# USB-UART.net
KiCad netlist of a schematic drawn in Altium Designer
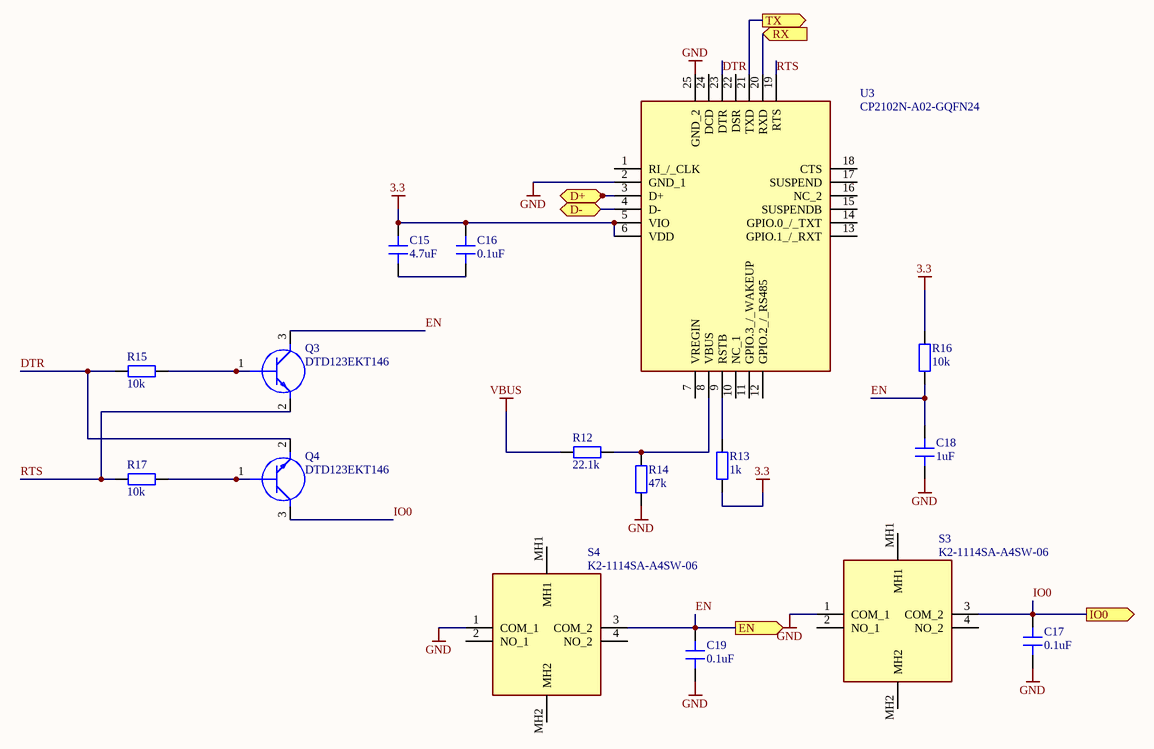
[diagram p0: USB-UART.SchDoc]

(export (version "E")
  (design (tool "Eeschema 10.0.6"))
  (components
    (comp (ref "C15")
      (value "4.7uF")
      (footprint "0603_CAP")
      (libsource (lib "passive_components") (part "C"))
    )
    (comp (ref "C16")
      (value "0.1uF")
      (footprint "0603_CAP")
      (libsource (lib "passive_components") (part "C"))
    )
    (comp (ref "C17")
      (value "0.1uF")
      (footprint "0603_CAP")
      (libsource (lib "passive_components") (part "C"))
    )
    (comp (ref "C18") (value "1uF") (footprint "0603_CAP") (libsource (lib "passive_components") (part "C")))
    (comp (ref "C19")
      (value "0.1uF")
      (footprint "0603_CAP")
      (libsource (lib "passive_components") (part "C"))
    )
    (comp (ref "Q3")
      (value "DTD123EKT146")
      (footprint "FP-SS8050-G-IPC_A")
      (description "Transistor BJT NPN")
      (fields (field (name "MOUSER PART NUMBER") "755-DTD123EKT146"))
      (libsource (lib "test") (part "DTD123EKT146"))
    )
    (comp (ref "Q4")
      (value "DTD123EKT146")
      (footprint "FP-SS8050-G-IPC_A")
      (description "Transistor BJT NPN")
      (fields (field (name "MOUSER PART NUMBER") "755-DTD123EKT146"))
      (libsource (lib "test") (part "DTD123EKT146"))
    )
    (comp (ref "R12")
      (value "22.1k")
      (footprint "0402_RES")
      (libsource (lib "passive_components") (part "R"))
    )
    (comp (ref "R13") (value "1k") (footprint "0402_RES") (libsource (lib "passive_components") (part "R")))
    (comp (ref "R14") (value "47k") (footprint "0402_RES") (libsource (lib "passive_components") (part "R")))
    (comp (ref "R15") (value "10k") (footprint "0402_RES") (libsource (lib "passive_components") (part "R")))
    (comp (ref "R16") (value "10k") (footprint "0402_RES") (libsource (lib "passive_components") (part "R")))
    (comp (ref "R17") (value "10k") (footprint "0402_RES") (libsource (lib "passive_components") (part "R")))
    (comp (ref "S3")
      (value "K2-1114SA-A4SW-06")
      (footprint "K21114SAA4SW06")
      (description "Switch")
      (libsource (lib "PushButton_v01") (part "K2-1114SA-A4SW-06"))
    )
    (comp (ref "S4")
      (value "K2-1114SA-A4SW-06")
      (footprint "K21114SAA4SW06")
      (description "Switch")
      (libsource (lib "PushButton_v01") (part "K2-1114SA-A4SW-06"))
    )
    (comp (ref "U3")
      (value "CP2102N-A02-GQFN24")
      (footprint "FP-CP2102N-A02-GQFN24-MFG")
      (description "Integrated Circuit")
      (fields (field (name "MOUSER PART NUMBER") "634-CP2102NA02GQFN24"))
      (libsource (lib "cp2102n_v01") (part "CP2102N-A02-GQFN24"))
    )
  )
  (nets
    (net (code "1") (name "/D+") (class "Default")
      (node (ref "U3") (pin "3") (pinfunction "D+_3") (pintype "passive"))
    )
    (net (code "2") (name "/D-") (class "Default")
      (node (ref "U3") (pin "4") (pinfunction "D-_4") (pintype "passive"))
    )
    (net (code "3") (name "/DTR") (class "Default")
      (node (ref "Q4") (pin "2") (pinfunction "E_2") (pintype "passive"))
      (node (ref "R15") (pin "1") (pinfunction "25_1") (pintype "passive"))
      (node (ref "U3") (pin "23") (pinfunction "DTR_23") (pintype "passive"))
    )
    (net (code "4") (name "/EN") (class "Default")
      (node (ref "C18") (pin "2") (pinfunction "28_2") (pintype "passive"))
      (node (ref "C19") (pin "1") (pinfunction "1_1") (pintype "passive"))
      (node (ref "Q3") (pin "3") (pinfunction "C_3") (pintype "passive"))
      (node (ref "R16") (pin "2") (pinfunction "26_2") (pintype "passive"))
      (node (ref "S4") (pin "3") (pinfunction "COM_2_3") (pintype "passive"))
    )
    (net (code "5") (name "/IO0") (class "Default")
      (node (ref "C17") (pin "1") (pinfunction "1_1") (pintype "passive"))
      (node (ref "Q4") (pin "3") (pinfunction "C_3") (pintype "passive"))
      (node (ref "S3") (pin "3") (pinfunction "COM_2_3") (pintype "passive"))
    )
    (net (code "6") (name "/RTS") (class "Default")
      (node (ref "Q3") (pin "2") (pinfunction "E_2") (pintype "passive"))
      (node (ref "R17") (pin "1") (pinfunction "25_1") (pintype "passive"))
      (node (ref "U3") (pin "19") (pinfunction "RTS_19") (pintype "passive"))
    )
    (net (code "7") (name "/RX") (class "Default")
      (node (ref "U3") (pin "20") (pinfunction "RXD_20") (pintype "passive"))
    )
    (net (code "8") (name "/TX") (class "Default")
      (node (ref "U3") (pin "21") (pinfunction "TXD_21") (pintype "passive"))
    )
    (net (code "9") (name "3.3") (class "Default")
      (node (ref "C15") (pin "1") (pinfunction "1_1") (pintype "passive"))
      (node (ref "C16") (pin "1") (pinfunction "1_1") (pintype "passive"))
      (node (ref "R13") (pin "2") (pinfunction "26_2") (pintype "passive"))
      (node (ref "R16") (pin "1") (pinfunction "25_1") (pintype "passive"))
      (node (ref "U3") (pin "5") (pinfunction "VIO_5") (pintype "passive"))
      (node (ref "U3") (pin "6") (pinfunction "VDD_6") (pintype "passive"))
    )
    (net (code "10") (name "GND") (class "Default")
      (node (ref "C17") (pin "2") (pinfunction "28_2") (pintype "passive"))
      (node (ref "C18") (pin "1") (pinfunction "1_1") (pintype "passive"))
      (node (ref "C19") (pin "2") (pinfunction "28_2") (pintype "passive"))
      (node (ref "R14") (pin "2") (pinfunction "26_2") (pintype "passive"))
      (node (ref "S3") (pin "1") (pinfunction "COM_1_1") (pintype "passive"))
      (node (ref "S4") (pin "1") (pinfunction "COM_1_1") (pintype "passive"))
      (node (ref "U3") (pin "2") (pinfunction "GND_1_2") (pintype "passive"))
      (node (ref "U3") (pin "25") (pinfunction "GND_2_25") (pintype "passive"))
    )
    (net (code "11") (name "Net-(C15-28)") (class "Default")
      (node (ref "C15") (pin "2") (pinfunction "28_2") (pintype "passive"))
      (node (ref "C16") (pin "2") (pinfunction "28_2") (pintype "passive"))
    )
    (net (code "12") (name "Net-(Q3-B)") (class "Default")
      (node (ref "Q3") (pin "1") (pinfunction "B_1") (pintype "passive"))
      (node (ref "R15") (pin "2") (pinfunction "26_2") (pintype "passive"))
    )
    (net (code "13") (name "Net-(Q4-B)") (class "Default")
      (node (ref "Q4") (pin "1") (pinfunction "B_1") (pintype "passive"))
      (node (ref "R17") (pin "2") (pinfunction "26_2") (pintype "passive"))
    )
    (net (code "14") (name "Net-(R12-25)") (class "Default")
      (node (ref "R12") (pin "1") (pinfunction "25_1") (pintype "passive"))
      (node (ref "R14") (pin "1") (pinfunction "25_1") (pintype "passive"))
      (node (ref "U3") (pin "8") (pinfunction "VBUS_8") (pintype "passive"))
    )
    (net (code "15") (name "Net-(R13-25)") (class "Default")
      (node (ref "R13") (pin "1") (pinfunction "25_1") (pintype "passive"))
      (node (ref "U3") (pin "9") (pinfunction "RSTB_9") (pintype "passive"))
    )
    (net (code "16") (name "VBUS") (class "Default")
      (node (ref "R12") (pin "2") (pinfunction "26_2") (pintype "passive"))
    )
    (net (code "17") (name "unconnected-(S3-NO_1-Pad2)") (class "Default")
      (node (ref "S3") (pin "2") (pinfunction "NO_1_2") (pintype "passive"))
    )
    (net (code "18") (name "unconnected-(S3-NO_2-Pad4)") (class "Default")
      (node (ref "S3") (pin "4") (pinfunction "NO_2_4") (pintype "passive"))
    )
    (net (code "19") (name "unconnected-(S3-PadMH1)") (class "Default")
      (node (ref "S3") (pin "MH1") (pinfunction "MH1_MH1") (pintype "passive"))
    )
    (net (code "20") (name "unconnected-(S3-PadMH2)") (class "Default")
      (node (ref "S3") (pin "MH2") (pinfunction "MH2_MH2") (pintype "passive"))
    )
    (net (code "21") (name "unconnected-(S4-NO_1-Pad2)") (class "Default")
      (node (ref "S4") (pin "2") (pinfunction "NO_1_2") (pintype "passive"))
    )
    (net (code "22") (name "unconnected-(S4-NO_2-Pad4)") (class "Default")
      (node (ref "S4") (pin "4") (pinfunction "NO_2_4") (pintype "passive"))
    )
    (net (code "23") (name "unconnected-(S4-PadMH1)") (class "Default")
      (node (ref "S4") (pin "MH1") (pinfunction "MH1_MH1") (pintype "passive"))
    )
    (net (code "24") (name "unconnected-(S4-PadMH2)") (class "Default")
      (node (ref "S4") (pin "MH2") (pinfunction "MH2_MH2") (pintype "passive"))
    )
    (net (code "25") (name "unconnected-(U3-CTS-Pad18)") (class "Default")
      (node (ref "U3") (pin "18") (pinfunction "CTS_18") (pintype "passive"))
    )
    (net (code "26") (name "unconnected-(U3-DCD-Pad24)") (class "Default")
      (node (ref "U3") (pin "24") (pinfunction "DCD_24") (pintype "passive"))
    )
    (net (code "27") (name "unconnected-(U3-DSR-Pad22)") (class "Default")
      (node (ref "U3") (pin "22") (pinfunction "DSR_22") (pintype "passive"))
    )
    (net (code "28") (name "unconnected-(U3-GPIO.0_{slash}_TXT-Pad14)") (class "Default")
      (node (ref "U3") (pin "14") (pinfunction "GPIO.0_/_TXT_14") (pintype "passive"))
    )
    (net (code "29") (name "unconnected-(U3-GPIO.1_{slash}_RXT-Pad13)") (class "Default")
      (node (ref "U3") (pin "13") (pinfunction "GPIO.1_/_RXT_13") (pintype "passive"))
    )
    (net (code "30") (name "unconnected-(U3-GPIO.2_{slash}_RS485-Pad12)") (class "Default")
      (node (ref "U3") (pin "12") (pinfunction "GPIO.2_/_RS485_12") (pintype "passive"))
    )
    (net (code "31") (name "unconnected-(U3-GPIO.3_{slash}_WAKEUP-Pad11)") (class "Default")
      (node (ref "U3") (pin "11") (pinfunction "GPIO.3_/_WAKEUP_11") (pintype "passive"))
    )
    (net (code "32") (name "unconnected-(U3-NC_1-Pad10)") (class "Default")
      (node (ref "U3") (pin "10") (pinfunction "NC_1_10") (pintype "passive"))
    )
    (net (code "33") (name "unconnected-(U3-NC_2-Pad16)") (class "Default")
      (node (ref "U3") (pin "16") (pinfunction "NC_2_16") (pintype "passive"))
    )
    (net (code "34") (name "unconnected-(U3-RI_{slash}_CLK-Pad1)") (class "Default")
      (node (ref "U3") (pin "1") (pinfunction "RI_/_CLK_1") (pintype "passive"))
    )
    (net (code "35") (name "unconnected-(U3-SUSPEND-Pad17)") (class "Default")
      (node (ref "U3") (pin "17") (pinfunction "SUSPEND_17") (pintype "passive"))
    )
    (net (code "36") (name "unconnected-(U3-SUSPENDB-Pad15)") (class "Default")
      (node (ref "U3") (pin "15") (pinfunction "SUSPENDB_15") (pintype "passive"))
    )
    (net (code "37") (name "unconnected-(U3-VREGIN-Pad7)") (class "Default")
      (node (ref "U3") (pin "7") (pinfunction "VREGIN_7") (pintype "passive"))
    )
  )
)
